# adapter.net
KiCad netlist of a schematic drawn in EAGLE
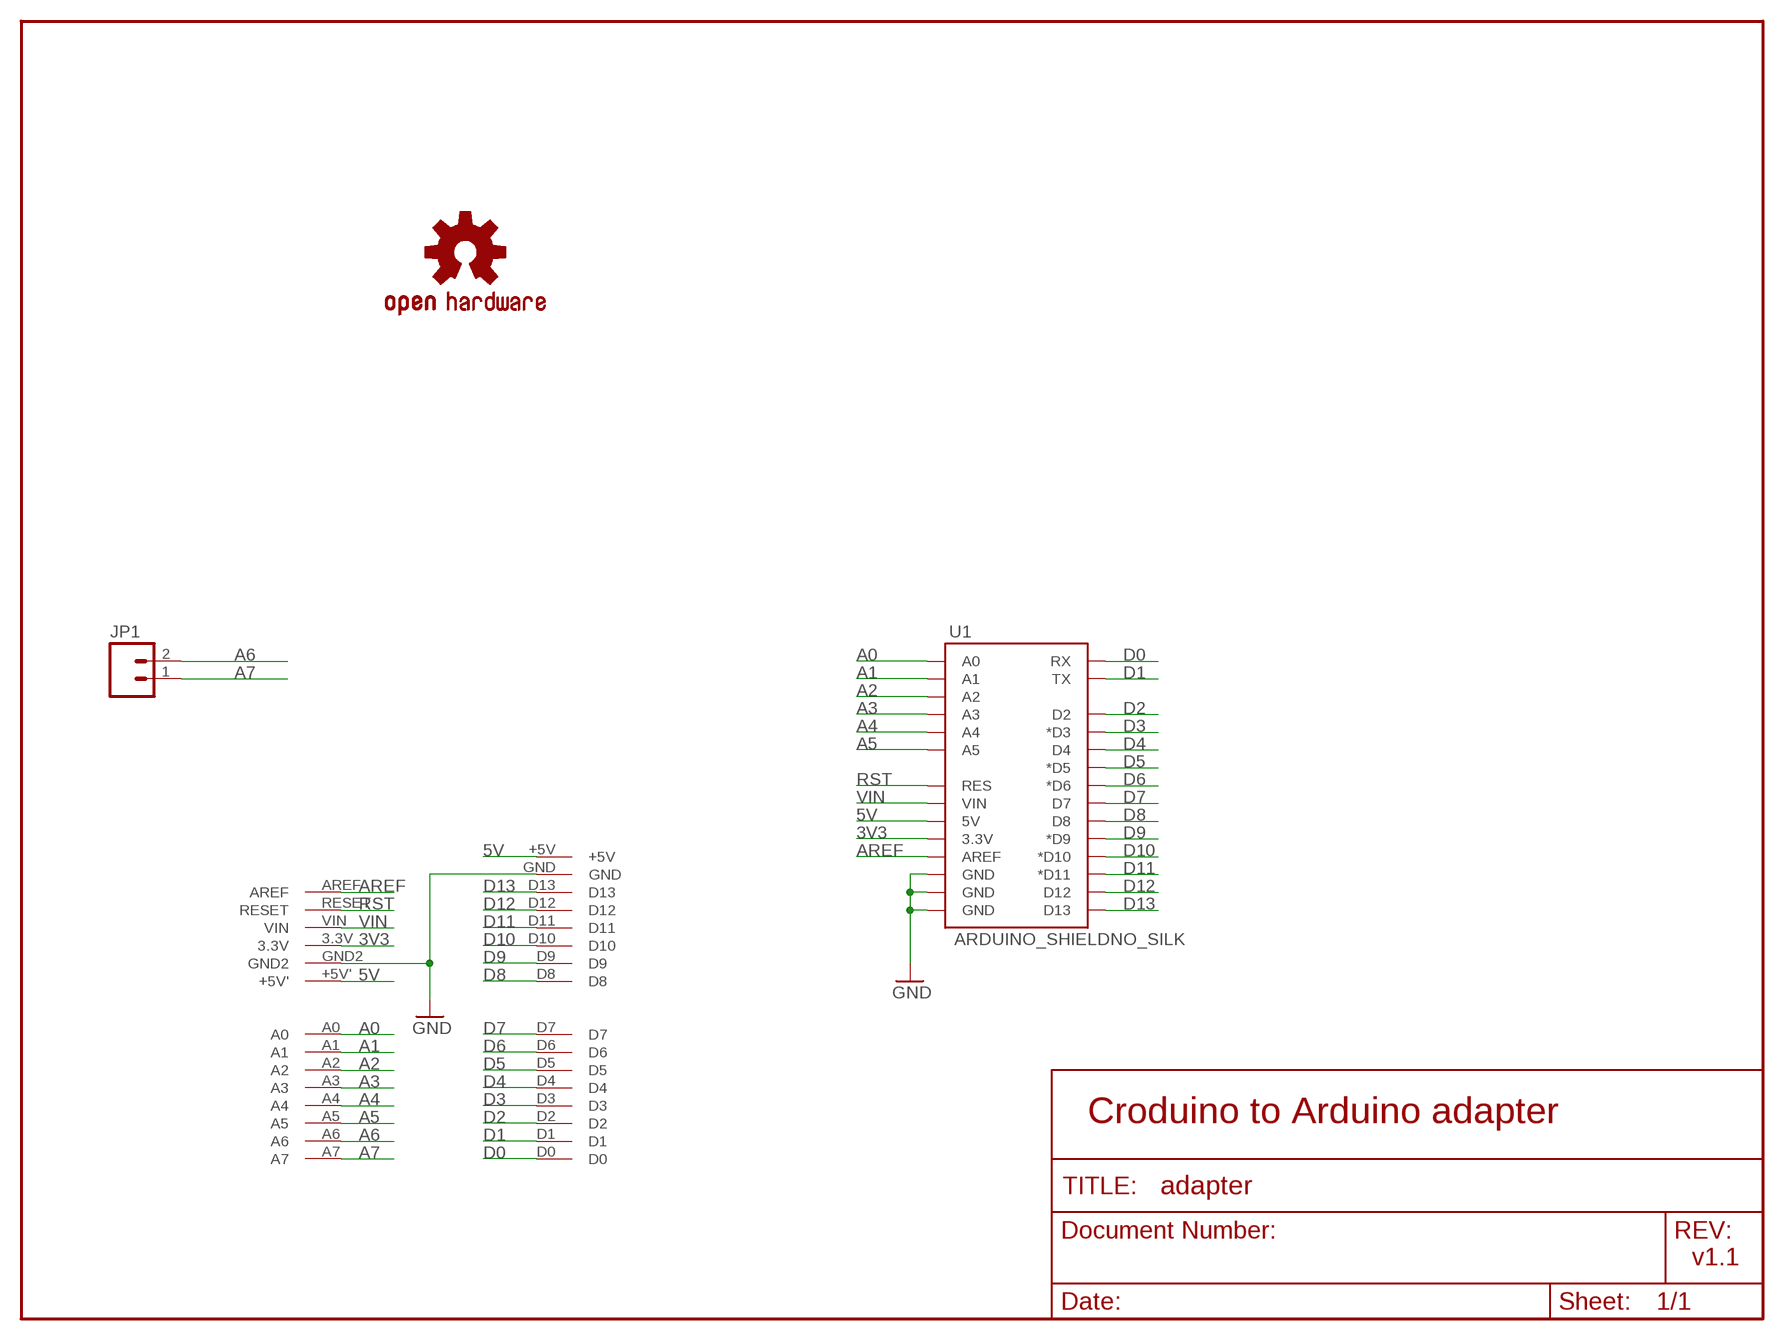
[diagram p0: schematic, sheet 1]

(export (version "E")
  (design (tool "Eeschema 10.0.6"))
  (components
    (comp (ref "JP1")
      (value "M02LOCK")
      (footprint "eagle-import:1X02_LOCK")
      (libsource (lib "eagle-import") (part "M02LOCK"))
    )
    (comp (ref "U$1")
      (value "CRODUINO_FOOTPRINT")
      (footprint "eagle-import:CRODUINO_FOOTPRINT")
      (libsource (lib "eagle-import") (part "CRODUINO_FOOTPRINT"))
    )
    (comp (ref "U$4")
      (value "OSHW-LOGOM")
      (footprint "eagle-import:OSHW-LOGO-M")
      (libsource (lib "eagle-import") (part "OSHW-LOGOM"))
    )
    (comp (ref "U1")
      (value "ARDUINO_SHIELDNO_SILK")
      (footprint "eagle-import:DUEMILANOVE_VIAS")
      (libsource (lib "eagle-import") (part "ARDUINO_SHIELDNO_SILK"))
    )
  )
  (nets
    (net (code "1") (name "/3V3") (class "Default")
      (node (ref "U$1") (pin "3.3V") (pinfunction "3.3V_3.3V") (pintype "bidirectional"))
      (node (ref "U1") (pin "3.3V") (pinfunction "3.3V_3.3V") (pintype "bidirectional"))
    )
    (net (code "2") (name "/5V") (class "Default")
      (node (ref "U$1") (pin "+5V") (pinfunction "+5V_+5V") (pintype "bidirectional"))
      (node (ref "U$1") (pin "+5V'") (pinfunction "+5V'_+5V'") (pintype "bidirectional"))
      (node (ref "U1") (pin "5V") (pinfunction "5V_5V") (pintype "bidirectional"))
    )
    (net (code "3") (name "/A0") (class "Default")
      (node (ref "U$1") (pin "A0") (pinfunction "A0_A0") (pintype "bidirectional"))
      (node (ref "U1") (pin "A0") (pinfunction "A0_A0") (pintype "bidirectional"))
    )
    (net (code "4") (name "/A1") (class "Default")
      (node (ref "U$1") (pin "A1") (pinfunction "A1_A1") (pintype "bidirectional"))
      (node (ref "U1") (pin "A1") (pinfunction "A1_A1") (pintype "bidirectional"))
    )
    (net (code "5") (name "/A2") (class "Default")
      (node (ref "U$1") (pin "A2") (pinfunction "A2_A2") (pintype "bidirectional"))
      (node (ref "U1") (pin "A2") (pinfunction "A2_A2") (pintype "bidirectional"))
    )
    (net (code "6") (name "/A3") (class "Default")
      (node (ref "U$1") (pin "A3") (pinfunction "A3_A3") (pintype "bidirectional"))
      (node (ref "U1") (pin "A3") (pinfunction "A3_A3") (pintype "bidirectional"))
    )
    (net (code "7") (name "/A4") (class "Default")
      (node (ref "U$1") (pin "A4") (pinfunction "A4_A4") (pintype "bidirectional"))
      (node (ref "U1") (pin "A4") (pinfunction "A4_A4") (pintype "bidirectional"))
    )
    (net (code "8") (name "/A5") (class "Default")
      (node (ref "U$1") (pin "A5") (pinfunction "A5_A5") (pintype "bidirectional"))
      (node (ref "U1") (pin "A5") (pinfunction "A5_A5") (pintype "bidirectional"))
    )
    (net (code "9") (name "/A6") (class "Default")
      (node (ref "JP1") (pin "2") (pinfunction "2_2") (pintype "passive"))
      (node (ref "U$1") (pin "A6") (pinfunction "A6_A6") (pintype "bidirectional"))
    )
    (net (code "10") (name "/A7") (class "Default")
      (node (ref "JP1") (pin "1") (pinfunction "1_1") (pintype "passive"))
      (node (ref "U$1") (pin "A7") (pinfunction "A7_A7") (pintype "bidirectional"))
    )
    (net (code "11") (name "/AREF") (class "Default")
      (node (ref "U$1") (pin "AREF") (pinfunction "AREF_AREF") (pintype "bidirectional"))
      (node (ref "U1") (pin "AREF") (pinfunction "AREF_AREF") (pintype "bidirectional"))
    )
    (net (code "12") (name "/D0") (class "Default")
      (node (ref "U$1") (pin "D0") (pinfunction "D0_D0") (pintype "bidirectional"))
      (node (ref "U1") (pin "RX") (pinfunction "RX_RX") (pintype "bidirectional"))
    )
    (net (code "13") (name "/D1") (class "Default")
      (node (ref "U$1") (pin "D1") (pinfunction "D1_D1") (pintype "bidirectional"))
      (node (ref "U1") (pin "TX") (pinfunction "TX_TX") (pintype "bidirectional"))
    )
    (net (code "14") (name "/D2") (class "Default")
      (node (ref "U$1") (pin "D2") (pinfunction "D2_D2") (pintype "bidirectional"))
      (node (ref "U1") (pin "D2") (pinfunction "D2_D2") (pintype "bidirectional"))
    )
    (net (code "15") (name "/D3") (class "Default")
      (node (ref "U$1") (pin "D3") (pinfunction "D3_D3") (pintype "bidirectional"))
      (node (ref "U1") (pin "D3") (pinfunction "*D3_D3") (pintype "bidirectional"))
    )
    (net (code "16") (name "/D4") (class "Default")
      (node (ref "U$1") (pin "D4") (pinfunction "D4_D4") (pintype "bidirectional"))
      (node (ref "U1") (pin "D4") (pinfunction "D4_D4") (pintype "bidirectional"))
    )
    (net (code "17") (name "/D5") (class "Default")
      (node (ref "U$1") (pin "D5") (pinfunction "D5_D5") (pintype "bidirectional"))
      (node (ref "U1") (pin "D5") (pinfunction "*D5_D5") (pintype "bidirectional"))
    )
    (net (code "18") (name "/D6") (class "Default")
      (node (ref "U$1") (pin "D6") (pinfunction "D6_D6") (pintype "bidirectional"))
      (node (ref "U1") (pin "D6") (pinfunction "*D6_D6") (pintype "bidirectional"))
    )
    (net (code "19") (name "/D7") (class "Default")
      (node (ref "U$1") (pin "D7") (pinfunction "D7_D7") (pintype "bidirectional"))
      (node (ref "U1") (pin "D7") (pinfunction "D7_D7") (pintype "bidirectional"))
    )
    (net (code "20") (name "/D8") (class "Default")
      (node (ref "U$1") (pin "D8") (pinfunction "D8_D8") (pintype "bidirectional"))
      (node (ref "U1") (pin "D8") (pinfunction "D8_D8") (pintype "bidirectional"))
    )
    (net (code "21") (name "/D9") (class "Default")
      (node (ref "U$1") (pin "D9") (pinfunction "D9_D9") (pintype "bidirectional"))
      (node (ref "U1") (pin "D9") (pinfunction "*D9_D9") (pintype "bidirectional"))
    )
    (net (code "22") (name "/D10") (class "Default")
      (node (ref "U$1") (pin "D10") (pinfunction "D10_D10") (pintype "bidirectional"))
      (node (ref "U1") (pin "D10") (pinfunction "*D10_D10") (pintype "bidirectional"))
    )
    (net (code "23") (name "/D11") (class "Default")
      (node (ref "U$1") (pin "D11") (pinfunction "D11_D11") (pintype "bidirectional"))
      (node (ref "U1") (pin "D11") (pinfunction "*D11_D11") (pintype "bidirectional"))
    )
    (net (code "24") (name "/D12") (class "Default")
      (node (ref "U$1") (pin "D12") (pinfunction "D12_D12") (pintype "bidirectional"))
      (node (ref "U1") (pin "D12") (pinfunction "D12_D12") (pintype "bidirectional"))
    )
    (net (code "25") (name "/D13") (class "Default")
      (node (ref "U$1") (pin "D13") (pinfunction "D13_D13") (pintype "bidirectional"))
      (node (ref "U1") (pin "D13") (pinfunction "D13_D13") (pintype "bidirectional"))
    )
    (net (code "26") (name "/RST") (class "Default")
      (node (ref "U$1") (pin "RESET") (pinfunction "RESET_RESET") (pintype "bidirectional"))
      (node (ref "U1") (pin "RES") (pinfunction "RES_RES") (pintype "bidirectional"))
    )
    (net (code "27") (name "/VIN") (class "Default")
      (node (ref "U$1") (pin "VIN") (pinfunction "VIN_VIN") (pintype "bidirectional"))
      (node (ref "U1") (pin "VIN") (pinfunction "VIN_VIN") (pintype "bidirectional"))
    )
    (net (code "28") (name "GND") (class "Default")
      (node (ref "U$1") (pin "GND") (pinfunction "GND_GND") (pintype "bidirectional"))
      (node (ref "U$1") (pin "GND2") (pinfunction "GND2_GND2") (pintype "bidirectional"))
      (node (ref "U1") (pin "GND@0") (pinfunction "GND_GND@0") (pintype "bidirectional"))
      (node (ref "U1") (pin "GND@1") (pinfunction "GND_GND@1") (pintype "bidirectional"))
      (node (ref "U1") (pin "GND@2") (pinfunction "GND_GND@2") (pintype "bidirectional"))
    )
  )
)
